# 1_P1_schdoc.net
KiCad netlist of a schematic drawn in Altium Designer
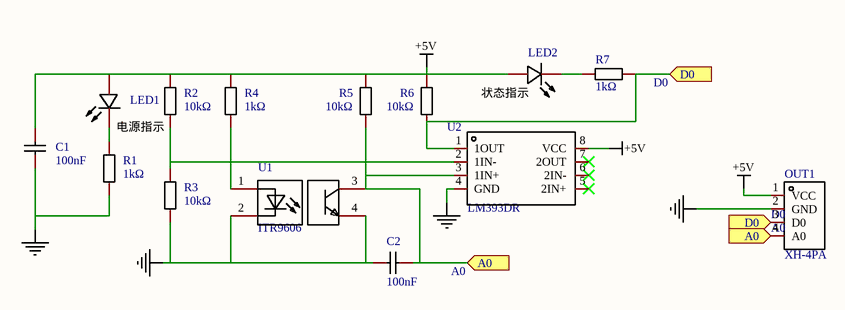
[diagram p0: 1_P1.schdoc.schdoc]

(export (version "E")
  (design (tool "Eeschema 10.0.6"))
  (components
    (comp (ref "C1")
      (value "100nF")
      (fields
        (field (name "NAME") "100nF")
        (field (name "MANUFACTURER") "FH(风华)")
        (field (name "MANUFACTURER PART") "0805B104K500NT")
        (field (name "TOLERANCE") "±10%")
      )
      (libsource (lib "altium-import") (part "root_1_0805B104K500NT_"))
    )
    (comp (ref "C2")
      (value "100nF")
      (fields
        (field (name "NAME") "100nF")
        (field (name "MANUFACTURER") "FH(风华)")
        (field (name "MANUFACTURER PART") "0805B104K500NT")
        (field (name "TOLERANCE") "±10%")
      )
      (libsource (lib "altium-import") (part "root_2_0805B104K500NT_"))
    )
    (comp (ref "LED1")
      (value "NCD0805R1")
      (fields (field (name "MANUFACTURER") "国星光电"))
      (libsource (lib "altium-import") (part "root_1_NCD0805R1_"))
    )
    (comp (ref "LED2")
      (value "NCD0805R1")
      (fields (field (name "MANUFACTURER") "国星光电"))
      (libsource (lib "altium-import") (part "root_2_NCD0805R1_"))
    )
    (comp (ref "OUT1")
      (value "XH-4PA")
      (fields (field (name "NAME") "XH-4PA") (field (name "MANUFACTURER") "ZHOURI(洲日)"))
      (libsource (lib "altium-import") (part "root_0_XH-4PA_"))
    )
    (comp (ref "R1")
      (value "1kΩ")
      (fields
        (field (name "NAME") "1kΩ")
        (field (name "MANUFACTURER") "UNI-ROYAL(厚声)")
        (field (name "MANUFACTURER PART") "0805W8F1001T5E")
        (field (name "TOLERANCE") "±1%")
      )
      (libsource (lib "altium-import") (part "root_1_0805W8F1001T5E_"))
    )
    (comp (ref "R2")
      (value "10kΩ")
      (fields
        (field (name "NAME") "10kΩ")
        (field (name "MANUFACTURER") "UNI-ROYAL(厚声)")
        (field (name "MANUFACTURER PART") "0805W8F1002T5E")
        (field (name "TOLERANCE") "±1%")
      )
      (libsource (lib "altium-import") (part "root_1_0805W8F1002T5E_C17414_"))
    )
    (comp (ref "R3")
      (value "10kΩ")
      (fields
        (field (name "NAME") "10kΩ")
        (field (name "MANUFACTURER") "UNI-ROYAL(厚声)")
        (field (name "MANUFACTURER PART") "0805W8F1002T5E")
        (field (name "TOLERANCE") "±1%")
      )
      (libsource (lib "altium-import") (part "root_1_0805W8F1002T5E_C17414_"))
    )
    (comp (ref "R4")
      (value "1kΩ")
      (fields
        (field (name "NAME") "1kΩ")
        (field (name "MANUFACTURER") "UNI-ROYAL(厚声)")
        (field (name "MANUFACTURER PART") "0805W8F1001T5E")
        (field (name "TOLERANCE") "±1%")
      )
      (libsource (lib "altium-import") (part "root_1_0805W8F1001T5E_"))
    )
    (comp (ref "R5")
      (value "10kΩ")
      (fields
        (field (name "NAME") "10kΩ")
        (field (name "MANUFACTURER") "UNI-ROYAL(厚声)")
        (field (name "MANUFACTURER PART") "0805W8F1002T5E")
        (field (name "TOLERANCE") "±1%")
      )
      (libsource (lib "altium-import") (part "root_1_0805W8F1002T5E_C17414_"))
    )
    (comp (ref "R6")
      (value "10kΩ")
      (fields
        (field (name "NAME") "10kΩ")
        (field (name "MANUFACTURER") "UNI-ROYAL(厚声)")
        (field (name "MANUFACTURER PART") "0805W8F1002T5E")
        (field (name "TOLERANCE") "±1%")
      )
      (libsource (lib "altium-import") (part "root_1_0805W8F1002T5E_C17414_"))
    )
    (comp (ref "R7")
      (value "1kΩ")
      (fields
        (field (name "NAME") "1kΩ")
        (field (name "MANUFACTURER") "UNI-ROYAL(厚声)")
        (field (name "MANUFACTURER PART") "0805W8F1001T5E")
        (field (name "TOLERANCE") "±1%")
      )
      (libsource (lib "altium-import") (part "root_2_0805W8F1001T5E_"))
    )
    (comp (ref "U1")
      (value "ITR9606")
      (fields (field (name "NAME") "ITR9606") (field (name "MANUFACTURER") "EVERLIGHT(亿光)"))
      (libsource (lib "altium-import") (part "root_0_ITR9606_"))
    )
    (comp (ref "U2")
      (value "LM393DR")
      (description "输入失调电压(Vos):5mV;输入偏置电流(Ib):250nA;")
      (fields (field (name "NAME") "LM393DR") (field (name "MANUFACTURER") "TI(德州仪器)"))
      (libsource (lib "altium-import") (part "root_0_LM393DR_"))
    )
  )
  (nets
    (net (code "1") (name "+5V") (class "Default")
      (node (ref "C1") (pin "2") (pinfunction "2_2") (pintype "passive"))
      (node (ref "LED1") (pin "1") (pinfunction "+_1") (pintype "passive"))
      (node (ref "LED2") (pin "1") (pinfunction "+_1") (pintype "passive"))
      (node (ref "OUT1") (pin "1") (pinfunction "VCC_1") (pintype "passive"))
      (node (ref "R2") (pin "2") (pinfunction "2_2") (pintype "passive"))
      (node (ref "R4") (pin "2") (pinfunction "2_2") (pintype "passive"))
      (node (ref "R5") (pin "2") (pinfunction "2_2") (pintype "passive"))
      (node (ref "R6") (pin "2") (pinfunction "2_2") (pintype "passive"))
      (node (ref "U2") (pin "8") (pinfunction "VCC_8") (pintype "passive"))
    )
    (net (code "2") (name "/A0") (class "Default")
      (node (ref "C2") (pin "1") (pinfunction "1_1") (pintype "passive"))
      (node (ref "OUT1") (pin "4") (pinfunction "A0_4") (pintype "passive"))
      (node (ref "R5") (pin "1") (pinfunction "1_1") (pintype "passive"))
      (node (ref "U1") (pin "3") (pinfunction "3_3") (pintype "passive"))
      (node (ref "U2") (pin "3") (pinfunction "1IN+_3") (pintype "passive"))
    )
    (net (code "3") (name "/D0") (class "Default")
      (node (ref "OUT1") (pin "3") (pinfunction "D0_3") (pintype "passive"))
      (node (ref "R6") (pin "1") (pinfunction "1_1") (pintype "passive"))
      (node (ref "R7") (pin "1") (pinfunction "1_1") (pintype "passive"))
      (node (ref "U2") (pin "1") (pinfunction "1OUT_1") (pintype "passive"))
    )
    (net (code "4") (name "<NO NET>") (class "Default")
      (node (ref "C1") (pin "1") (pinfunction "1_1") (pintype "passive"))
      (node (ref "C2") (pin "2") (pinfunction "2_2") (pintype "passive"))
      (node (ref "OUT1") (pin "2") (pinfunction "GND_2") (pintype "passive"))
      (node (ref "R1") (pin "1") (pinfunction "1_1") (pintype "passive"))
      (node (ref "R3") (pin "1") (pinfunction "1_1") (pintype "passive"))
      (node (ref "U1") (pin "2") (pinfunction "2_2") (pintype "passive"))
      (node (ref "U1") (pin "4") (pinfunction "4_4") (pintype "passive"))
      (node (ref "U2") (pin "4") (pinfunction "GND_4") (pintype "passive"))
    )
    (net (code "5") (name "Net-(LED1--)") (class "Default")
      (node (ref "LED1") (pin "2") (pinfunction "-_2") (pintype "passive"))
      (node (ref "R1") (pin "2") (pinfunction "2_2") (pintype "passive"))
    )
    (net (code "6") (name "Net-(LED2--)") (class "Default")
      (node (ref "LED2") (pin "2") (pinfunction "-_2") (pintype "passive"))
      (node (ref "R7") (pin "2") (pinfunction "2_2") (pintype "passive"))
    )
    (net (code "7") (name "Net-(R4-Pad1)") (class "Default")
      (node (ref "R4") (pin "1") (pinfunction "1_1") (pintype "passive"))
      (node (ref "U1") (pin "1") (pinfunction "1_1") (pintype "passive"))
    )
    (net (code "8") (name "Net-(U2-1IN-)") (class "Default")
      (node (ref "R2") (pin "1") (pinfunction "1_1") (pintype "passive"))
      (node (ref "R3") (pin "2") (pinfunction "2_2") (pintype "passive"))
      (node (ref "U2") (pin "2") (pinfunction "1IN-_2") (pintype "passive"))
    )
    (net (code "9") (name "unconnected-(U2-2IN+-Pad5)") (class "Default")
      (node (ref "U2") (pin "5") (pinfunction "2IN+_5") (pintype "passive+no_connect"))
    )
    (net (code "10") (name "unconnected-(U2-2IN--Pad6)") (class "Default")
      (node (ref "U2") (pin "6") (pinfunction "2IN-_6") (pintype "passive+no_connect"))
    )
    (net (code "11") (name "unconnected-(U2-2OUT-Pad7)") (class "Default")
      (node (ref "U2") (pin "7") (pinfunction "2OUT_7") (pintype "passive+no_connect"))
    )
  )
)
